# 15321_3.net
KiCad netlist of a schematic drawn in EAGLE
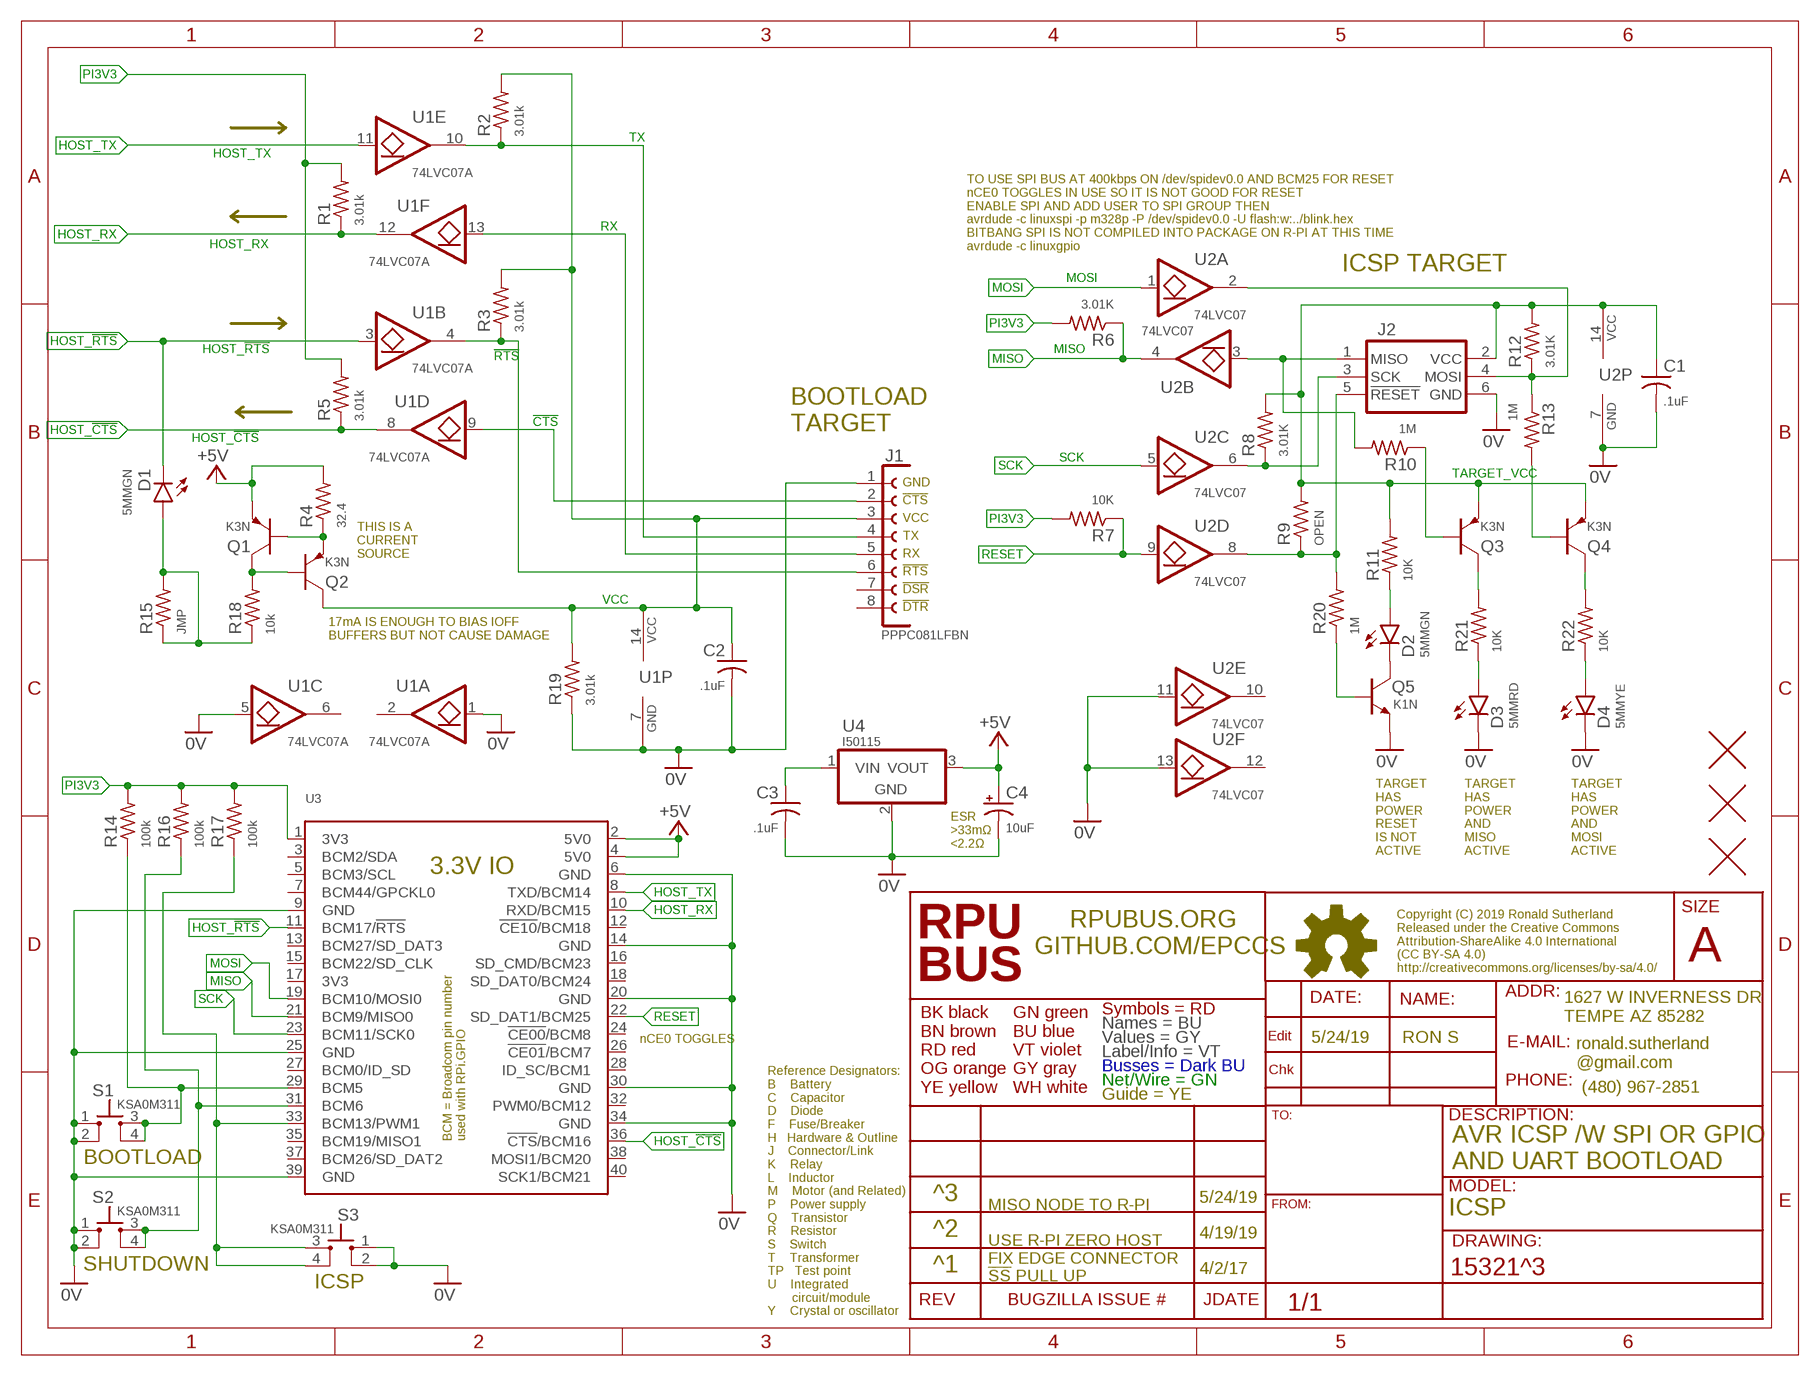
[diagram p0: schematic, sheet 1]

(export (version "E")
  (design (tool "Eeschema 10.0.6"))
  (components
    (comp (ref "C1")
      (value ".1uF")
      (footprint "eagle-import:C0603(1608)")
      (libsource (lib "eagle-import") (part "CC0603A"))
    )
    (comp (ref "C2")
      (value ".1uF")
      (footprint "eagle-import:C0603(1608)")
      (libsource (lib "eagle-import") (part "CC0603A"))
    )
    (comp (ref "C3")
      (value ".1uF")
      (footprint "eagle-import:C0603(1608)")
      (libsource (lib "eagle-import") (part "CC0603A"))
    )
    (comp (ref "C4")
      (value "10uF")
      (footprint "eagle-import:3216")
      (libsource (lib "eagle-import") (part "CT1206"))
    )
    (comp (ref "D1")
      (value "5MMGN")
      (footprint "eagle-import:LED5MM")
      (libsource (lib "eagle-import") (part "LED5MM"))
    )
    (comp (ref "D2")
      (value "5MMGN")
      (footprint "eagle-import:LED5MM")
      (libsource (lib "eagle-import") (part "LED5MM"))
    )
    (comp (ref "D3")
      (value "5MMRD")
      (footprint "eagle-import:LED5MM")
      (libsource (lib "eagle-import") (part "LED5MM"))
    )
    (comp (ref "D4")
      (value "5MMYE")
      (footprint "eagle-import:LED5MM")
      (libsource (lib "eagle-import") (part "LED5MM"))
    )
    (comp (ref "J1")
      (value "PPPC081LFBN")
      (footprint "eagle-import:F1X8")
      (libsource (lib "eagle-import") (part "F1X8"))
    )
    (comp (ref "J2")
      (value "ISP-SPIEDG")
      (footprint "eagle-import:ISP-EDG")
      (libsource (lib "eagle-import") (part "ISP-SPIEDG"))
    )
    (comp (ref "Q1")
      (value "K3N")
      (footprint "eagle-import:SOT23")
      (libsource (lib "eagle-import") (part "PNPSOT23"))
    )
    (comp (ref "Q2")
      (value "K3N")
      (footprint "eagle-import:SOT23")
      (libsource (lib "eagle-import") (part "PNPSOT23"))
    )
    (comp (ref "Q3")
      (value "K3N")
      (footprint "eagle-import:SOT23")
      (libsource (lib "eagle-import") (part "PNPSOT23"))
    )
    (comp (ref "Q4")
      (value "K3N")
      (footprint "eagle-import:SOT23")
      (libsource (lib "eagle-import") (part "PNPSOT23"))
    )
    (comp (ref "Q5")
      (value "K1N")
      (footprint "eagle-import:SOT23")
      (libsource (lib "eagle-import") (part "NPNSOT23"))
    )
    (comp (ref "R1")
      (value "3.01k")
      (footprint "eagle-import:C0805(2012)")
      (libsource (lib "eagle-import") (part "R0805"))
    )
    (comp (ref "R2")
      (value "3.01k")
      (footprint "eagle-import:C0805(2012)")
      (libsource (lib "eagle-import") (part "R0805"))
    )
    (comp (ref "R3")
      (value "3.01k")
      (footprint "eagle-import:C0805(2012)")
      (libsource (lib "eagle-import") (part "R0805"))
    )
    (comp (ref "R4")
      (value "32.4")
      (footprint "eagle-import:C0805(2012)")
      (libsource (lib "eagle-import") (part "R0805"))
    )
    (comp (ref "R5")
      (value "3.01k")
      (footprint "eagle-import:C0805(2012)")
      (libsource (lib "eagle-import") (part "R0805"))
    )
    (comp (ref "R6")
      (value "3.01K")
      (footprint "eagle-import:C0805(2012)")
      (libsource (lib "eagle-import") (part "R0805"))
    )
    (comp (ref "R7")
      (value "10K")
      (footprint "eagle-import:C0805(2012)")
      (libsource (lib "eagle-import") (part "R0805"))
    )
    (comp (ref "R8")
      (value "3.01K")
      (footprint "eagle-import:C0805(2012)")
      (libsource (lib "eagle-import") (part "R0805"))
    )
    (comp (ref "R9")
      (value "OPEN")
      (footprint "eagle-import:C0805(2012)")
      (libsource (lib "eagle-import") (part "R0805"))
    )
    (comp (ref "R10")
      (value "1M")
      (footprint "eagle-import:C0805(2012)")
      (libsource (lib "eagle-import") (part "R0805"))
    )
    (comp (ref "R11")
      (value "10K")
      (footprint "eagle-import:C0805(2012)")
      (libsource (lib "eagle-import") (part "R0805"))
    )
    (comp (ref "R12")
      (value "3.01K")
      (footprint "eagle-import:C0805(2012)")
      (libsource (lib "eagle-import") (part "R0805"))
    )
    (comp (ref "R13")
      (value "1M")
      (footprint "eagle-import:C0805(2012)")
      (libsource (lib "eagle-import") (part "R0805"))
    )
    (comp (ref "R14")
      (value "100k")
      (footprint "eagle-import:C0805(2012)")
      (libsource (lib "eagle-import") (part "R0805"))
    )
    (comp (ref "R15")
      (value "JMP")
      (footprint "eagle-import:C0805(2012)")
      (libsource (lib "eagle-import") (part "R0805"))
    )
    (comp (ref "R16")
      (value "100k")
      (footprint "eagle-import:C0805(2012)")
      (libsource (lib "eagle-import") (part "R0805"))
    )
    (comp (ref "R17")
      (value "100k")
      (footprint "eagle-import:C0805(2012)")
      (libsource (lib "eagle-import") (part "R0805"))
    )
    (comp (ref "R18")
      (value "10k")
      (footprint "eagle-import:C0805(2012)")
      (libsource (lib "eagle-import") (part "R0805"))
    )
    (comp (ref "R19")
      (value "3.01k")
      (footprint "eagle-import:C0805(2012)")
      (libsource (lib "eagle-import") (part "R0805"))
    )
    (comp (ref "R20")
      (value "1M")
      (footprint "eagle-import:C0805(2012)")
      (libsource (lib "eagle-import") (part "R0805"))
    )
    (comp (ref "R21")
      (value "10K")
      (footprint "eagle-import:C0805(2012)")
      (libsource (lib "eagle-import") (part "R0805"))
    )
    (comp (ref "R22")
      (value "10K")
      (footprint "eagle-import:C0805(2012)")
      (libsource (lib "eagle-import") (part "R0805"))
    )
    (comp (ref "S1")
      (value "KSA0M311")
      (footprint "eagle-import:0M311")
      (libsource (lib "eagle-import") (part "KSA0M311"))
    )
    (comp (ref "S2")
      (value "KSA0M311")
      (footprint "eagle-import:0M311")
      (libsource (lib "eagle-import") (part "KSA0M311"))
    )
    (comp (ref "S3")
      (value "KSA0M311")
      (footprint "eagle-import:0M311")
      (libsource (lib "eagle-import") (part "KSA0M311"))
    )
    (comp (ref "U$2")
      (value "FIDUCIAL1.27")
      (footprint "eagle-import:FIDUCIAL-1.27")
      (libsource (lib "eagle-import") (part "FIDUCIAL1.27"))
    )
    (comp (ref "U$3")
      (value "FIDUCIAL1.27")
      (footprint "eagle-import:FIDUCIAL-1.27")
      (libsource (lib "eagle-import") (part "FIDUCIAL1.27"))
    )
    (comp (ref "U$4")
      (value "FIDUCIAL1.27")
      (footprint "eagle-import:FIDUCIAL-1.27")
      (libsource (lib "eagle-import") (part "FIDUCIAL1.27"))
    )
    (comp (ref "U1")
      (value "74LVC07A")
      (footprint "eagle-import:14SOIC")
      (libsource (lib "eagle-import") (part "7407D"))
    )
    (comp (ref "U2")
      (value "74LVC07")
      (footprint "eagle-import:14SOIC")
      (libsource (lib "eagle-import") (part "7407D"))
    )
    (comp (ref "U3")
      (value "RPI-ZERO")
      (footprint "eagle-import:RASPI_ZERO_H40PIN")
      (libsource (lib "eagle-import") (part "RPI-ZERO"))
    )
    (comp (ref "U4")
      (value "I50115")
      (footprint "eagle-import:OKI-78SR-H")
      (libsource (lib "eagle-import") (part "OKI-78SR-H"))
    )
  )
  (nets
    (net (code "1") (name "+5V") (class "Default")
      (node (ref "C4") (pin "+") (pinfunction "+_+") (pintype "passive"))
      (node (ref "Q1") (pin "E") (pinfunction "E_E") (pintype "passive"))
      (node (ref "R4") (pin "2") (pinfunction "2_2") (pintype "passive"))
      (node (ref "U3") (pin "2") (pinfunction "5V0_2") (pintype "power_in"))
      (node (ref "U3") (pin "4") (pinfunction "5V0_4") (pintype "power_in"))
      (node (ref "U4") (pin "3") (pinfunction "VOUT_3") (pintype "passive"))
    )
    (net (code "2") (name "/3V3") (class "Default")
      (node (ref "U3") (pin "17") (pinfunction "3V3_17") (pintype "power_in"))
    )
    (net (code "3") (name "/HOST_~{CTS}") (class "Default")
      (node (ref "R5") (pin "1") (pinfunction "1_1") (pintype "passive"))
      (node (ref "U1") (pin "8") (pinfunction "O_8") (pintype "open_collector"))
      (node (ref "U3") (pin "36") (pinfunction "~{CTS}/BCM16_36") (pintype "bidirectional"))
    )
    (net (code "4") (name "/HOST_~{RTS}") (class "Default")
      (node (ref "D1") (pin "K") (pinfunction "K_K") (pintype "passive"))
      (node (ref "U1") (pin "3") (pinfunction "I_3") (pintype "input"))
      (node (ref "U3") (pin "11") (pinfunction "BCM17/~{RTS}_11") (pintype "bidirectional"))
    )
    (net (code "5") (name "/RX") (class "Default")
      (node (ref "J1") (pin "5") (pinfunction "5_5") (pintype "passive"))
      (node (ref "U1") (pin "13") (pinfunction "I_13") (pintype "input"))
    )
    (net (code "6") (name "/TARGET_VCC") (class "Default")
      (node (ref "C1") (pin "1") (pinfunction "1_1") (pintype "passive"))
      (node (ref "J2") (pin "2") (pinfunction "VCC_2") (pintype "bidirectional"))
      (node (ref "Q3") (pin "E") (pinfunction "E_E") (pintype "passive"))
      (node (ref "Q4") (pin "E") (pinfunction "E_E") (pintype "passive"))
      (node (ref "R11") (pin "2") (pinfunction "2_2") (pintype "passive"))
      (node (ref "R12") (pin "2") (pinfunction "2_2") (pintype "passive"))
      (node (ref "R8") (pin "2") (pinfunction "2_2") (pintype "passive"))
      (node (ref "R9") (pin "2") (pinfunction "2_2") (pintype "passive"))
      (node (ref "U2") (pin "14") (pinfunction "VCC_14") (pintype "power_in"))
    )
    (net (code "7") (name "/TX") (class "Default")
      (node (ref "J1") (pin "4") (pinfunction "4_4") (pintype "passive"))
      (node (ref "R2") (pin "1") (pinfunction "1_1") (pintype "passive"))
      (node (ref "U1") (pin "10") (pinfunction "O_10") (pintype "open_collector"))
    )
    (net (code "8") (name "/VCC") (class "Default")
      (node (ref "C2") (pin "1") (pinfunction "1_1") (pintype "passive"))
      (node (ref "J1") (pin "3") (pinfunction "3_3") (pintype "passive"))
      (node (ref "Q2") (pin "C") (pinfunction "C_C") (pintype "passive"))
      (node (ref "R19") (pin "2") (pinfunction "2_2") (pintype "passive"))
      (node (ref "R2") (pin "2") (pinfunction "2_2") (pintype "passive"))
      (node (ref "R3") (pin "2") (pinfunction "2_2") (pintype "passive"))
      (node (ref "U1") (pin "14") (pinfunction "VCC_14") (pintype "power_in"))
    )
    (net (code "9") (name "/~{CTS}") (class "Default")
      (node (ref "J1") (pin "2") (pinfunction "2_2") (pintype "passive"))
      (node (ref "U1") (pin "9") (pinfunction "I_9") (pintype "input"))
    )
    (net (code "10") (name "/~{RTS}") (class "Default")
      (node (ref "J1") (pin "6") (pinfunction "6_6") (pintype "passive"))
      (node (ref "R3") (pin "1") (pinfunction "1_1") (pintype "passive"))
      (node (ref "U1") (pin "4") (pinfunction "O_4") (pintype "open_collector"))
    )
    (net (code "11") (name "0V") (class "Default")
      (node (ref "C1") (pin "2") (pinfunction "2_2") (pintype "passive"))
      (node (ref "C2") (pin "2") (pinfunction "2_2") (pintype "passive"))
      (node (ref "C3") (pin "2") (pinfunction "2_2") (pintype "passive"))
      (node (ref "C4") (pin "-") (pinfunction "-_-") (pintype "passive"))
      (node (ref "D3") (pin "K") (pinfunction "K_K") (pintype "passive"))
      (node (ref "D4") (pin "K") (pinfunction "K_K") (pintype "passive"))
      (node (ref "J1") (pin "1") (pinfunction "1_1") (pintype "passive"))
      (node (ref "J2") (pin "6") (pinfunction "GND_6") (pintype "bidirectional"))
      (node (ref "Q5") (pin "E") (pinfunction "E_E") (pintype "passive"))
      (node (ref "R19") (pin "1") (pinfunction "1_1") (pintype "passive"))
      (node (ref "S1") (pin "1") (pinfunction "1_1") (pintype "passive"))
      (node (ref "S1") (pin "2") (pinfunction "2_2") (pintype "passive"))
      (node (ref "S2") (pin "1") (pinfunction "1_1") (pintype "passive"))
      (node (ref "S2") (pin "2") (pinfunction "2_2") (pintype "passive"))
      (node (ref "S3") (pin "1") (pinfunction "1_1") (pintype "passive"))
      (node (ref "S3") (pin "2") (pinfunction "2_2") (pintype "passive"))
      (node (ref "U1") (pin "1") (pinfunction "I_1") (pintype "input"))
      (node (ref "U1") (pin "5") (pinfunction "I_5") (pintype "input"))
      (node (ref "U1") (pin "7") (pinfunction "GND_7") (pintype "power_in"))
      (node (ref "U2") (pin "11") (pinfunction "I_11") (pintype "input"))
      (node (ref "U2") (pin "13") (pinfunction "I_13") (pintype "input"))
      (node (ref "U2") (pin "7") (pinfunction "GND_7") (pintype "power_in"))
      (node (ref "U3") (pin "14") (pinfunction "GND_14") (pintype "power_in"))
      (node (ref "U3") (pin "20") (pinfunction "GND_20") (pintype "power_in"))
      (node (ref "U3") (pin "25") (pinfunction "GND_25") (pintype "power_in"))
      (node (ref "U3") (pin "30") (pinfunction "GND_30") (pintype "power_in"))
      (node (ref "U3") (pin "34") (pinfunction "GND_34") (pintype "power_in"))
      (node (ref "U3") (pin "39") (pinfunction "GND_39") (pintype "power_in"))
      (node (ref "U3") (pin "6") (pinfunction "GND_6") (pintype "power_in"))
      (node (ref "U3") (pin "9") (pinfunction "GND_9") (pintype "power_in"))
      (node (ref "U4") (pin "2") (pinfunction "GND_2") (pintype "passive"))
    )
    (net (code "12") (name "HOST_RX") (class "Default")
      (node (ref "R1") (pin "1") (pinfunction "1_1") (pintype "passive"))
      (node (ref "U1") (pin "12") (pinfunction "O_12") (pintype "open_collector"))
      (node (ref "U3") (pin "10") (pinfunction "RXD/BCM15_10") (pintype "bidirectional"))
    )
    (net (code "13") (name "HOST_TX") (class "Default")
      (node (ref "U1") (pin "11") (pinfunction "I_11") (pintype "input"))
      (node (ref "U3") (pin "8") (pinfunction "TXD/BCM14_8") (pintype "bidirectional"))
    )
    (net (code "14") (name "MISO") (class "Default")
      (node (ref "R6") (pin "1") (pinfunction "1_1") (pintype "passive"))
      (node (ref "U2") (pin "4") (pinfunction "O_4") (pintype "open_collector"))
      (node (ref "U3") (pin "21") (pinfunction "BCM9/MISO0_21") (pintype "bidirectional"))
    )
    (net (code "15") (name "MOSI") (class "Default")
      (node (ref "U2") (pin "1") (pinfunction "I_1") (pintype "input"))
      (node (ref "U3") (pin "19") (pinfunction "BCM10/MOSI0_19") (pintype "bidirectional"))
    )
    (net (code "16") (name "Net-(D1-PadA)") (class "Default")
      (node (ref "D1") (pin "A") (pinfunction "A_A") (pintype "passive"))
      (node (ref "R15") (pin "1") (pinfunction "1_1") (pintype "passive"))
      (node (ref "R15") (pin "2") (pinfunction "2_2") (pintype "passive"))
      (node (ref "R18") (pin "1") (pinfunction "1_1") (pintype "passive"))
    )
    (net (code "17") (name "Net-(D2-PadA)") (class "Default")
      (node (ref "D2") (pin "A") (pinfunction "A_A") (pintype "passive"))
      (node (ref "R11") (pin "1") (pinfunction "1_1") (pintype "passive"))
    )
    (net (code "18") (name "Net-(D2-PadK)") (class "Default")
      (node (ref "D2") (pin "K") (pinfunction "K_K") (pintype "passive"))
      (node (ref "Q5") (pin "C") (pinfunction "C_C") (pintype "passive"))
    )
    (net (code "19") (name "Net-(D3-PadA)") (class "Default")
      (node (ref "D3") (pin "A") (pinfunction "A_A") (pintype "passive"))
      (node (ref "R21") (pin "1") (pinfunction "1_1") (pintype "passive"))
    )
    (net (code "20") (name "Net-(D4-PadA)") (class "Default")
      (node (ref "D4") (pin "A") (pinfunction "A_A") (pintype "passive"))
      (node (ref "R22") (pin "1") (pinfunction "1_1") (pintype "passive"))
    )
    (net (code "21") (name "Net-(J2-MISO)") (class "Default")
      (node (ref "J2") (pin "1") (pinfunction "MISO_1") (pintype "bidirectional"))
      (node (ref "R10") (pin "2") (pinfunction "2_2") (pintype "passive"))
      (node (ref "U2") (pin "3") (pinfunction "I_3") (pintype "input"))
    )
    (net (code "22") (name "Net-(J2-MOSI)") (class "Default")
      (node (ref "J2") (pin "4") (pinfunction "MOSI_4") (pintype "bidirectional"))
      (node (ref "R12") (pin "1") (pinfunction "1_1") (pintype "passive"))
      (node (ref "R13") (pin "1") (pinfunction "1_1") (pintype "passive"))
      (node (ref "U2") (pin "2") (pinfunction "O_2") (pintype "open_collector"))
    )
    (net (code "23") (name "Net-(J2-SCK)") (class "Default")
      (node (ref "J2") (pin "3") (pinfunction "SCK_3") (pintype "bidirectional"))
      (node (ref "R8") (pin "1") (pinfunction "1_1") (pintype "passive"))
      (node (ref "U2") (pin "6") (pinfunction "O_6") (pintype "open_collector"))
    )
    (net (code "24") (name "Net-(J2-~{RESET})") (class "Default")
      (node (ref "J2") (pin "5") (pinfunction "~{RESET}_5") (pintype "bidirectional"))
      (node (ref "R20") (pin "2") (pinfunction "2_2") (pintype "passive"))
      (node (ref "R9") (pin "1") (pinfunction "1_1") (pintype "passive"))
      (node (ref "U2") (pin "8") (pinfunction "O_8") (pintype "open_collector"))
    )
    (net (code "25") (name "Net-(Q1-PadB)") (class "Default")
      (node (ref "Q1") (pin "B") (pinfunction "B_B") (pintype "passive"))
      (node (ref "Q2") (pin "E") (pinfunction "E_E") (pintype "passive"))
      (node (ref "R4") (pin "1") (pinfunction "1_1") (pintype "passive"))
    )
    (net (code "26") (name "Net-(Q1-PadC)") (class "Default")
      (node (ref "Q1") (pin "C") (pinfunction "C_C") (pintype "passive"))
      (node (ref "Q2") (pin "B") (pinfunction "B_B") (pintype "passive"))
      (node (ref "R18") (pin "2") (pinfunction "2_2") (pintype "passive"))
    )
    (net (code "27") (name "Net-(Q3-PadB)") (class "Default")
      (node (ref "Q3") (pin "B") (pinfunction "B_B") (pintype "passive"))
      (node (ref "R10") (pin "1") (pinfunction "1_1") (pintype "passive"))
    )
    (net (code "28") (name "Net-(Q3-PadC)") (class "Default")
      (node (ref "Q3") (pin "C") (pinfunction "C_C") (pintype "passive"))
      (node (ref "R21") (pin "2") (pinfunction "2_2") (pintype "passive"))
    )
    (net (code "29") (name "Net-(Q4-PadB)") (class "Default")
      (node (ref "Q4") (pin "B") (pinfunction "B_B") (pintype "passive"))
      (node (ref "R13") (pin "2") (pinfunction "2_2") (pintype "passive"))
    )
    (net (code "30") (name "Net-(Q4-PadC)") (class "Default")
      (node (ref "Q4") (pin "C") (pinfunction "C_C") (pintype "passive"))
      (node (ref "R22") (pin "2") (pinfunction "2_2") (pintype "passive"))
    )
    (net (code "31") (name "Net-(Q5-PadB)") (class "Default")
      (node (ref "Q5") (pin "B") (pinfunction "B_B") (pintype "passive"))
      (node (ref "R20") (pin "1") (pinfunction "1_1") (pintype "passive"))
    )
    (net (code "32") (name "Net-(U3-BCM5)") (class "Default")
      (node (ref "R14") (pin "1") (pinfunction "1_1") (pintype "passive"))
      (node (ref "S1") (pin "3") (pinfunction "3_3") (pintype "passive"))
      (node (ref "S1") (pin "4") (pinfunction "4_4") (pintype "passive"))
      (node (ref "U3") (pin "29") (pinfunction "BCM5_29") (pintype "bidirectional"))
    )
    (net (code "33") (name "Net-(U3-BCM6)") (class "Default")
      (node (ref "R16") (pin "1") (pinfunction "1_1") (pintype "passive"))
      (node (ref "S2") (pin "3") (pinfunction "3_3") (pintype "passive"))
      (node (ref "S2") (pin "4") (pinfunction "4_4") (pintype "passive"))
      (node (ref "U3") (pin "31") (pinfunction "BCM6_31") (pintype "bidirectional"))
    )
    (net (code "34") (name "Net-(U3-BCM13{slash}PWM1)") (class "Default")
      (node (ref "R17") (pin "1") (pinfunction "1_1") (pintype "passive"))
      (node (ref "S3") (pin "3") (pinfunction "3_3") (pintype "passive"))
      (node (ref "S3") (pin "4") (pinfunction "4_4") (pintype "passive"))
      (node (ref "U3") (pin "33") (pinfunction "BCM13/PWM1_33") (pintype "bidirectional"))
    )
    (net (code "35") (name "Net-(U4-VIN)") (class "Default")
      (node (ref "C3") (pin "1") (pinfunction "1_1") (pintype "passive"))
      (node (ref "U4") (pin "1") (pinfunction "VIN_1") (pintype "passive"))
    )
    (net (code "36") (name "PI3V3") (class "Default")
      (node (ref "R1") (pin "2") (pinfunction "2_2") (pintype "passive"))
      (node (ref "R14") (pin "2") (pinfunction "2_2") (pintype "passive"))
      (node (ref "R16") (pin "2") (pinfunction "2_2") (pintype "passive"))
      (node (ref "R17") (pin "2") (pinfunction "2_2") (pintype "passive"))
      (node (ref "R5") (pin "2") (pinfunction "2_2") (pintype "passive"))
      (node (ref "R6") (pin "2") (pinfunction "2_2") (pintype "passive"))
      (node (ref "R7") (pin "2") (pinfunction "2_2") (pintype "passive"))
      (node (ref "U3") (pin "1") (pinfunction "3V3_1") (pintype "power_in"))
    )
    (net (code "37") (name "RESET") (class "Default")
      (node (ref "R7") (pin "1") (pinfunction "1_1") (pintype "passive"))
      (node (ref "U2") (pin "9") (pinfunction "I_9") (pintype "input"))
      (node (ref "U3") (pin "22") (pinfunction "SD_DAT1/BCM25_22") (pintype "bidirectional"))
    )
    (net (code "38") (name "SCK") (class "Default")
      (node (ref "U2") (pin "5") (pinfunction "I_5") (pintype "input"))
      (node (ref "U3") (pin "23") (pinfunction "BCM11/SCK0_23") (pintype "bidirectional"))
    )
    (net (code "39") (name "unconnected-(J1-Pad7)") (class "Default")
      (node (ref "J1") (pin "7") (pinfunction "7_7") (pintype "passive"))
    )
    (net (code "40") (name "unconnected-(J1-Pad8)") (class "Default")
      (node (ref "J1") (pin "8") (pinfunction "8_8") (pintype "passive"))
    )
    (net (code "41") (name "unconnected-(U1A-O-Pad2)") (class "Default")
      (node (ref "U1") (pin "2") (pinfunction "O_2") (pintype "open_collector"))
    )
    (net (code "42") (name "unconnected-(U1C-O-Pad6)") (class "Default")
      (node (ref "U1") (pin "6") (pinfunction "O_6") (pintype "open_collector"))
    )
    (net (code "43") (name "unconnected-(U2E-O-Pad10)") (class "Default")
      (node (ref "U2") (pin "10") (pinfunction "O_10") (pintype "open_collector"))
    )
    (net (code "44") (name "unconnected-(U2F-O-Pad12)") (class "Default")
      (node (ref "U2") (pin "12") (pinfunction "O_12") (pintype "open_collector"))
    )
    (net (code "45") (name "unconnected-(U3-BCM0{slash}ID_SD-Pad27)") (class "Default")
      (node (ref "U3") (pin "27") (pinfunction "BCM0/ID_SD_27") (pintype "bidirectional"))
    )
    (net (code "46") (name "unconnected-(U3-BCM2{slash}SDA-Pad3)") (class "Default")
      (node (ref "U3") (pin "3") (pinfunction "BCM2/SDA_3") (pintype "bidirectional"))
    )
    (net (code "47") (name "unconnected-(U3-BCM3{slash}SCL-Pad5)") (class "Default")
      (node (ref "U3") (pin "5") (pinfunction "BCM3/SCL_5") (pintype "bidirectional"))
    )
    (net (code "48") (name "unconnected-(U3-BCM19{slash}MISO1-Pad35)") (class "Default")
      (node (ref "U3") (pin "35") (pinfunction "BCM19/MISO1_35") (pintype "bidirectional"))
    )
    (net (code "49") (name "unconnected-(U3-BCM22{slash}SD_CLK-Pad15)") (class "Default")
      (node (ref "U3") (pin "15") (pinfunction "BCM22/SD_CLK_15") (pintype "bidirectional"))
    )
    (net (code "50") (name "unconnected-(U3-BCM26{slash}SD_DAT2-Pad37)") (class "Default")
      (node (ref "U3") (pin "37") (pinfunction "BCM26/SD_DAT2_37") (pintype "bidirectional"))
    )
    (net (code "51") (name "unconnected-(U3-BCM27{slash}SD_DAT3-Pad13)") (class "Default")
      (node (ref "U3") (pin "13") (pinfunction "BCM27/SD_DAT3_13") (pintype "bidirectional"))
    )
    (net (code "52") (name "unconnected-(U3-BCM44{slash}GPCKL0-Pad7)") (class "Default")
      (node (ref "U3") (pin "7") (pinfunction "BCM44/GPCKL0_7") (pintype "bidirectional"))
    )
    (net (code "53") (name "unconnected-(U3-ID_SC{slash}BCM1-Pad28)") (class "Default")
      (node (ref "U3") (pin "28") (pinfunction "ID_SC/BCM1_28") (pintype "bidirectional"))
    )
    (net (code "54") (name "unconnected-(U3-MOSI1{slash}BCM20-Pad38)") (class "Default")
      (node (ref "U3") (pin "38") (pinfunction "MOSI1/BCM20_38") (pintype "bidirectional"))
    )
    (net (code "55") (name "unconnected-(U3-PWM0{slash}BCM12-Pad32)") (class "Default")
      (node (ref "U3") (pin "32") (pinfunction "PWM0/BCM12_32") (pintype "bidirectional"))
    )
    (net (code "56") (name "unconnected-(U3-SCK1{slash}BCM21-Pad40)") (class "Default")
      (node (ref "U3") (pin "40") (pinfunction "SCK1/BCM21_40") (pintype "bidirectional"))
    )
    (net (code "57") (name "unconnected-(U3-SD_CMD{slash}BCM23-Pad16)") (class "Default")
      (node (ref "U3") (pin "16") (pinfunction "SD_CMD/BCM23_16") (pintype "bidirectional"))
    )
    (net (code "58") (name "unconnected-(U3-SD_DAT0{slash}BCM24-Pad18)") (class "Default")
      (node (ref "U3") (pin "18") (pinfunction "SD_DAT0/BCM24_18") (pintype "bidirectional"))
    )
    (net (code "59") (name "unconnected-(U3-~{CE00}{slash}BCM8-Pad24)") (class "Default")
      (node (ref "U3") (pin "24") (pinfunction "~{CE00}/BCM8_24") (pintype "bidirectional"))
    )
    (net (code "60") (name "unconnected-(U3-~{CE01}{slash}BCM7-Pad26)") (class "Default")
      (node (ref "U3") (pin "26") (pinfunction "~{CE01}/BCM7_26") (pintype "bidirectional"))
    )
    (net (code "61") (name "unconnected-(U3-~{CE10}{slash}BCM18-Pad12)") (class "Default")
      (node (ref "U3") (pin "12") (pinfunction "~{CE10}/BCM18_12") (pintype "bidirectional"))
    )
  )
)
